# Stepper_Hat_Trio_V3_9.net
KiCad netlist of a schematic drawn in EasyEDA
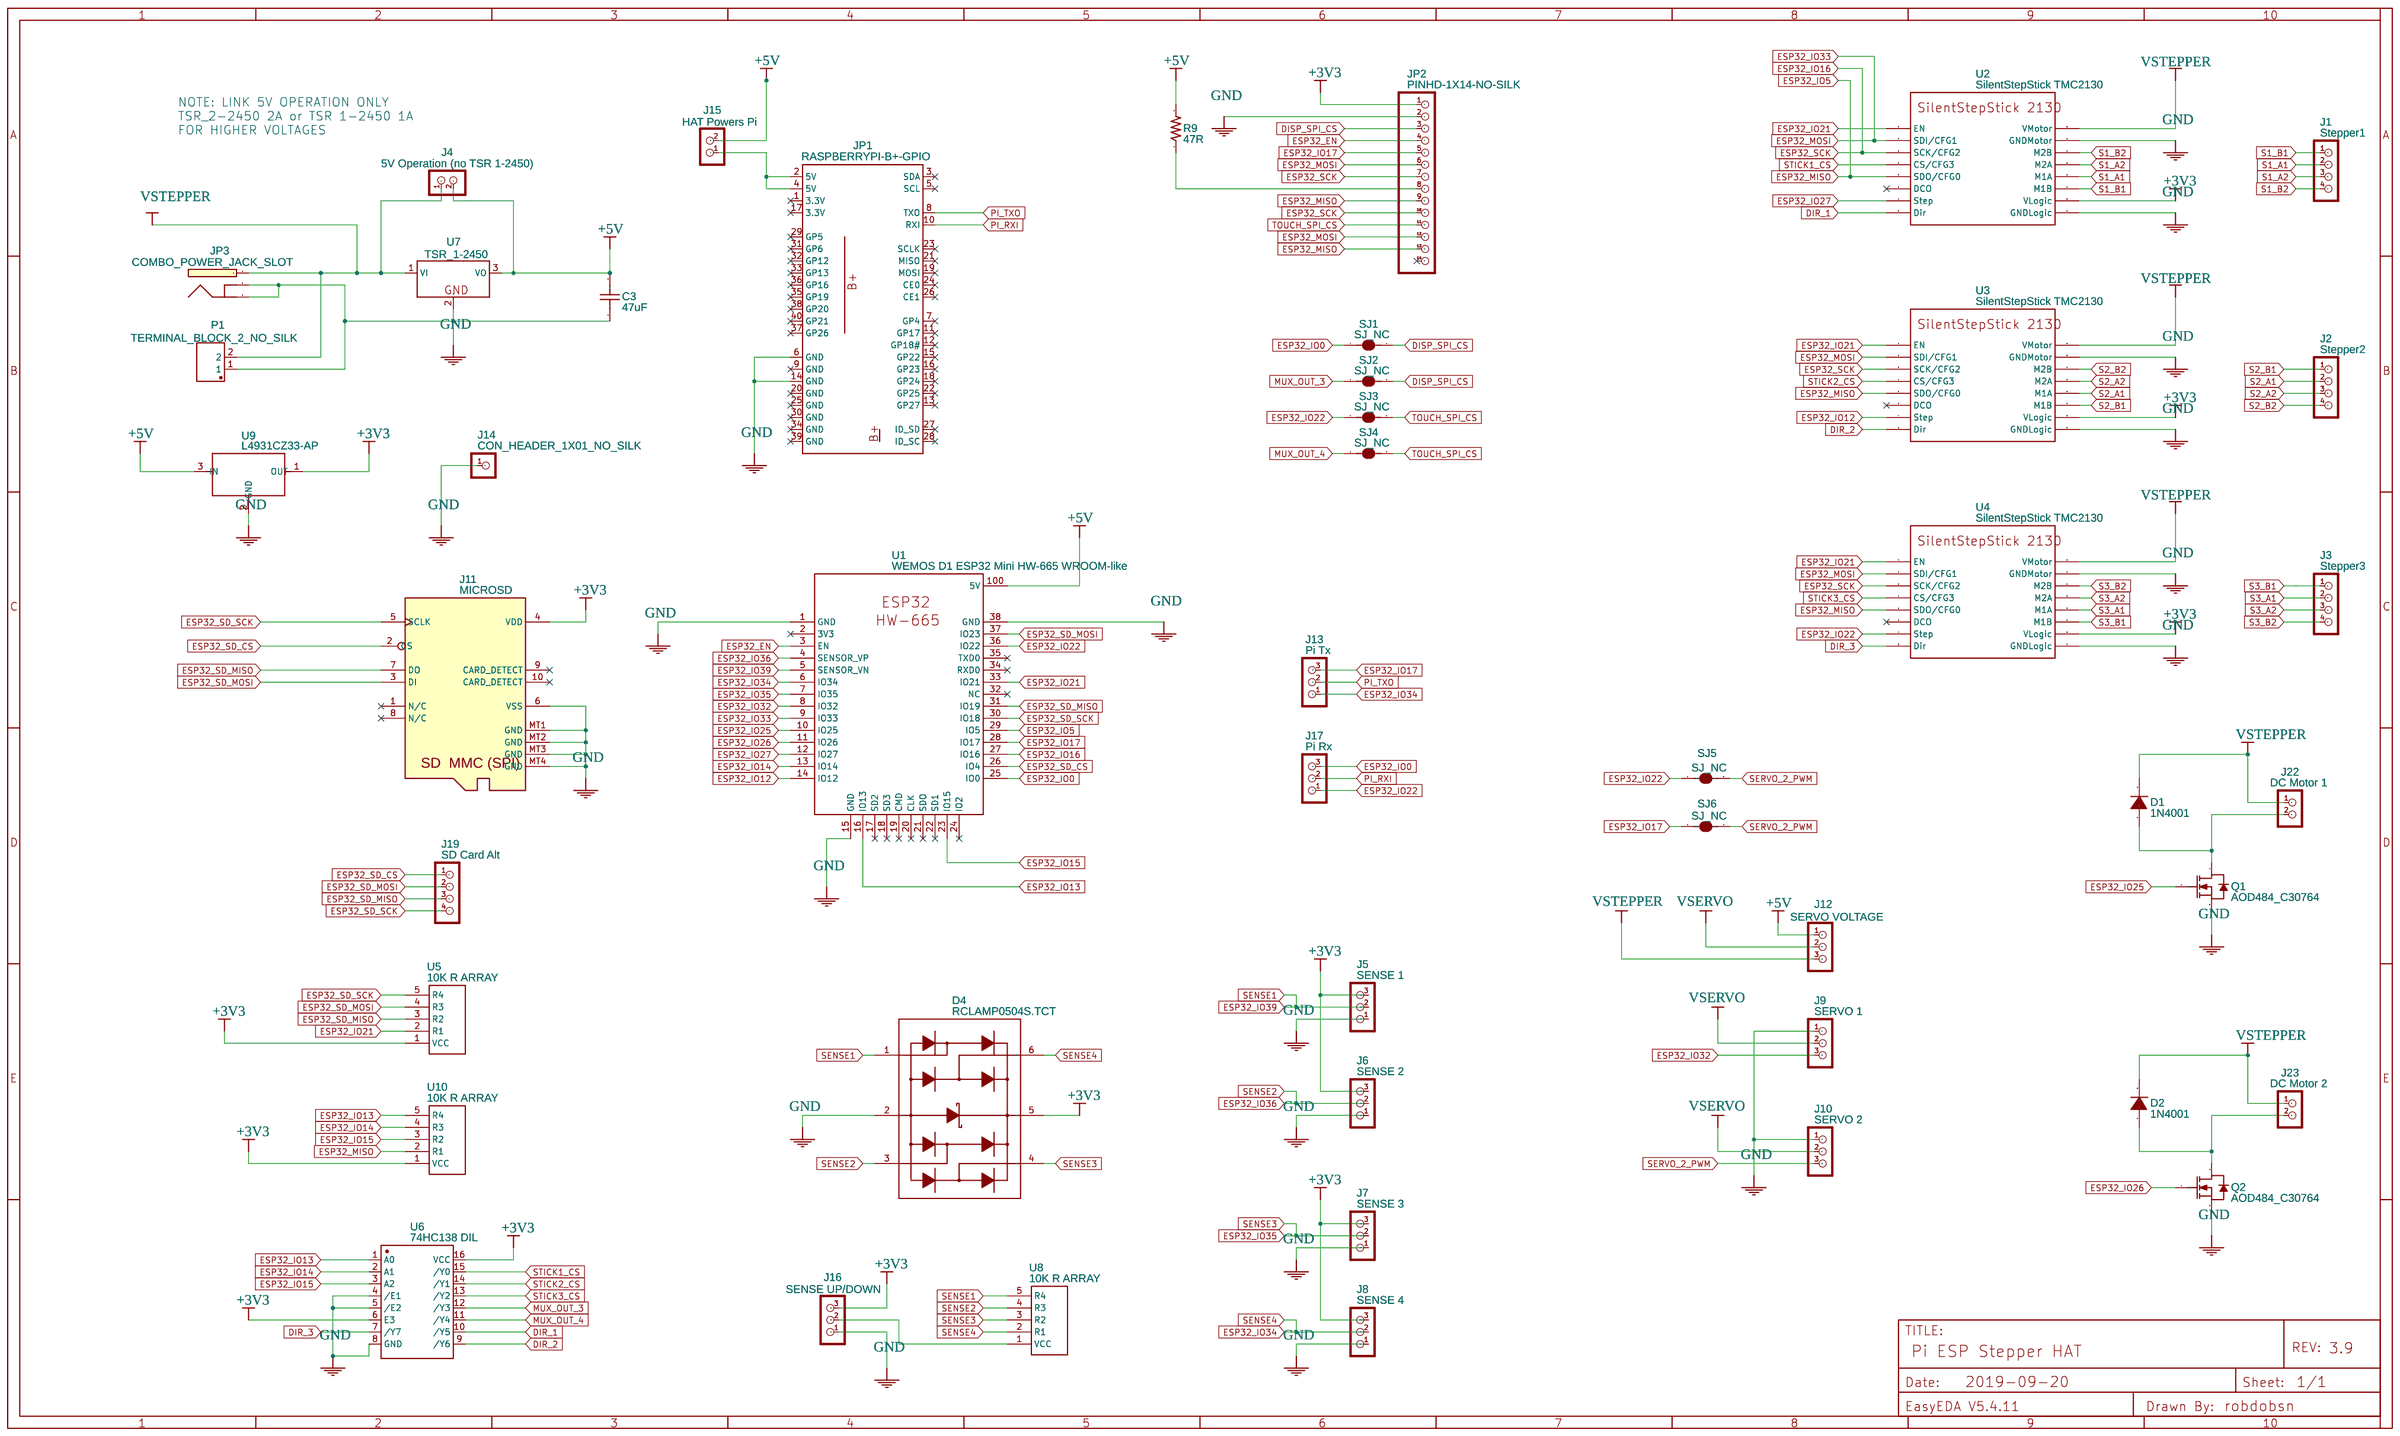
[diagram p0: schematic sheet]

(export (version "E")
  (design (tool "Eeschema 10.0.6"))
  (components
    (comp (ref "C3")
      (value "47uF")
      (fields
        (field (name "BOM_Manufacturer Part") "GRM31CR60J107ME39L")
        (field (name "BOM_Supplier Part") "C77085")
      )
      (libsource (lib "") (part "GRM31CR60J107ME39L"))
    )
    (comp (ref "D1")
      (value "1N4001")
      (fields (field (name "BOM_Supplier Part") "C82804"))
      (libsource (lib "") (part "Unknown_1690_660"))
    )
    (comp (ref "D2")
      (value "1N4001")
      (fields (field (name "BOM_Supplier Part") "C82804"))
      (libsource (lib "") (part "Unknown_1690_910"))
    )
    (comp (ref "D4")
      (value "RCLAMP0504S.TCT")
      (fields (field (name "BOM_Supplier Part") "C132260"))
      (libsource (lib "") (part "Unknown_710_920"))
    )
    (comp (ref "J1")
      (value "Stepper1")
      (fields (field (name "BOM_Manufacturer Part") "?"))
      (libsource (lib "") (part "Unknown_1840_130"))
    )
    (comp (ref "J2")
      (value "Stepper2")
      (fields (field (name "BOM_Manufacturer Part") "?"))
      (libsource (lib "") (part "Unknown_1840_310"))
    )
    (comp (ref "J3")
      (value "Stepper3")
      (fields (field (name "BOM_Manufacturer Part") "?"))
      (libsource (lib "") (part "Unknown_1840_490"))
    )
    (comp (ref "J4")
      (value "5V Operation (no TSR 1-2450)")
      (fields (field (name "BOM_Manufacturer Part") "?"))
      (libsource (lib "") (part "Unknown_280_150"))
    )
    (comp (ref "J5")
      (value "SENSE 1")
      (fields (field (name "BOM_Manufacturer Part") "?"))
      (libsource (lib "") (part "Unknown_1050_830"))
    )
    (comp (ref "J6")
      (value "SENSE 2")
      (fields (field (name "BOM_Manufacturer Part") "?"))
      (libsource (lib "") (part "Unknown_1050_910"))
    )
    (comp (ref "J7")
      (value "SENSE 3")
      (fields (field (name "BOM_Manufacturer Part") "?"))
      (libsource (lib "") (part "Unknown_1050_1020"))
    )
    (comp (ref "J8")
      (value "SENSE 4")
      (fields (field (name "BOM_Manufacturer Part") "?"))
      (libsource (lib "") (part "Unknown_1050_1100"))
    )
    (comp (ref "J9")
      (value "SERVO 1")
      (fields (field (name "BOM_Manufacturer Part") "?"))
      (libsource (lib "") (part "Unknown_1420_860"))
    )
    (comp (ref "J10")
      (value "SERVO 2")
      (fields (field (name "BOM_Manufacturer Part") "?"))
      (libsource (lib "") (part "Unknown_1420_950"))
    )
    (comp (ref "J11")
      (value "MICROSD")
      (fields (field (name "BOM_Manufacturer Part") "?") (field (name "BOM_Supplier Part") "WM11190CT-ND"))
      (libsource (lib "") (part "Unknown_310_540"))
    )
    (comp (ref "J12")
      (value "SERVO VOLTAGE")
      (fields (field (name "BOM_Manufacturer Part") "?"))
      (libsource (lib "") (part "Unknown_1420_780"))
    )
    (comp (ref "J13")
      (value "Pi Tx")
      (fields (field (name "BOM_Manufacturer Part") "?"))
      (libsource (lib "") (part "Unknown_1010_560"))
    )
    (comp (ref "J14") (value "CON_HEADER_1X01_NO_SILK") (libsource (lib "") (part "Unknown_320_380")))
    (comp (ref "J15")
      (value "HAT Powers Pi")
      (fields (field (name "BOM_Manufacturer Part") "?"))
      (libsource (lib "") (part "Unknown_510_120"))
    )
    (comp (ref "J16")
      (value "SENSE UP/DOWN")
      (fields (field (name "BOM_Manufacturer Part") "?"))
      (libsource (lib "") (part "Unknown_610_1090"))
    )
    (comp (ref "J17")
      (value "Pi Rx")
      (fields (field (name "BOM_Manufacturer Part") "?"))
      (libsource (lib "") (part "Unknown_1010_640"))
    )
    (comp (ref "J19") (value "SD Card Alt") (libsource (lib "") (part "Unknown_280_730")))
    (comp (ref "J22")
      (value "DC Motor 1")
      (fields (field (name "BOM_Manufacturer Part") "?"))
      (libsource (lib "") (part "Unknown_1810_660"))
    )
    (comp (ref "J23")
      (value "DC Motor 2")
      (fields (field (name "BOM_Manufacturer Part") "?"))
      (libsource (lib "") (part "Unknown_1810_910"))
    )
    (comp (ref "JP1")
      (value "RASPBERRYPI-B+-GPIO")
      (fields (field (name "BOM_Manufacturer Part") "?"))
      (libsource (lib "") (part "Unknown_630_240"))
    )
    (comp (ref "JP2") (value "PINHD-1X14-NO-SILK") (libsource (lib "") (part "Unknown_1090_150")))
    (comp (ref "JP3") (value "COMBO_POWER_JACK_SLOT") (libsource (lib "") (part "Unknown_100_230")))
    (comp (ref "P1")
      (value "TERMINAL_BLOCK_2_NO_SILK")
      (fields
        (field (name "BOM_Manufacturer Part") "WJ2EDGV-5.08-2P")
        (field (name "BOM_Supplier Part") "C8461")
      )
      (libsource (lib "") (part "Unknown_100_310"))
    )
    (comp (ref "Q1")
      (value "AOD484_C30764")
      (fields (field (name "BOM_Manufacturer Part") "AOD484") (field (name "BOM_Supplier Part") "C30764"))
      (libsource (lib "") (part "Unknown_1740_730"))
    )
    (comp (ref "Q2")
      (value "AOD484_C30764")
      (fields (field (name "BOM_Manufacturer Part") "AOD484") (field (name "BOM_Supplier Part") "C30764"))
      (libsource (lib "") (part "Unknown_1740_980"))
    )
    (comp (ref "R9")
      (value "47R")
      (fields (field (name "BOM_Manufacturer Part") "?"))
      (libsource (lib "") (part "Unknown_890_100"))
    )
    (comp (ref "SJ1") (value "SJ_NC") (libsource (lib "") (part "Unknown_1050_280")))
    (comp (ref "SJ2") (value "SJ_NC") (libsource (lib "") (part "Unknown_1050_310")))
    (comp (ref "SJ3") (value "SJ_NC") (libsource (lib "") (part "Unknown_1050_340")))
    (comp (ref "SJ4") (value "SJ_NC") (libsource (lib "") (part "Unknown_1050_370")))
    (comp (ref "SJ5") (value "SJ_NC") (libsource (lib "") (part "Unknown_1330_640")))
    (comp (ref "SJ6") (value "SJ_NC") (libsource (lib "") (part "Unknown_1330_680")))
    (comp (ref "U1")
      (value "WEMOS D1 ESP32 Mini HW-665 WROOM-like")
      (fields (field (name "BOM_Supplier Part") "WEMOS_D1_ESP32"))
      (libsource (lib "") (part "Unknown_570_660"))
    )
    (comp (ref "U2")
      (value "SilentStepStick TMC2130")
      (fields (field (name "BOM_Supplier Part") "20160027"))
      (libsource (lib "") (part "Unknown_1480_100"))
    )
    (comp (ref "U3")
      (value "SilentStepStick TMC2130")
      (fields (field (name "BOM_Supplier Part") "20160027"))
      (libsource (lib "") (part "Unknown_1480_280"))
    )
    (comp (ref "U4")
      (value "SilentStepStick TMC2130")
      (fields (field (name "BOM_Supplier Part") "20160027"))
      (libsource (lib "") (part "Unknown_1480_460"))
    )
    (comp (ref "U5")
      (value "10K R ARRAY")
      (fields
        (field (name "BOM_Manufacturer Part") "4605X-AP1-103LF")
        (field (name "BOM_Supplier Part") "652-4605X-AP1-103LF")
      )
      (libsource (lib "") (part "Unknown_270_820"))
    )
    (comp (ref "U6")
      (value "74HC138 DIL")
      (fields (field (name "BOM_Manufacturer Part") "74HC138") (field (name "BOM_Supplier Part") "C2913"))
      (libsource (lib "") (part "Unknown_260_1060"))
    )
    (comp (ref "U7")
      (value "TSR_1-2450")
      (fields
        (field (name "BOM_Manufacturer Part") "TSR 1-2433")
        (field (name "BOM_Supplier Part") "1696319")
      )
      (libsource (lib "") (part "Unknown_290_220"))
    )
    (comp (ref "U8")
      (value "10K R ARRAY")
      (fields
        (field (name "BOM_Manufacturer Part") "4605X-AP1-103LF")
        (field (name "BOM_Supplier Part") "652-4605X-AP1-103LF")
      )
      (libsource (lib "") (part "Unknown_770_1070"))
    )
    (comp (ref "U9") (value "L4931CZ33-AP") (libsource (lib "") (part "Unknown_120_400")))
    (comp (ref "U10")
      (value "10K R ARRAY")
      (fields
        (field (name "BOM_Manufacturer Part") "4605X-AP1-103LF")
        (field (name "BOM_Supplier Part") "652-4605X-AP1-103LF")
      )
      (libsource (lib "") (part "Unknown_270_920"))
    )
  )
  (nets
    (net (code "1") (name "+3V3") (class "Default")
      (node (ref "D4") (pin "5") (pinfunction "5_5") (pintype "input"))
      (node (ref "J11") (pin "4") (pinfunction "VDD_4") (pintype "unspecified"))
      (node (ref "J16") (pin "3") (pinfunction "3_3") (pintype "unspecified"))
      (node (ref "J5") (pin "3") (pinfunction "3_3") (pintype "unspecified"))
      (node (ref "J6") (pin "3") (pinfunction "3_3") (pintype "unspecified"))
      (node (ref "J7") (pin "3") (pinfunction "3_3") (pintype "unspecified"))
      (node (ref "J8") (pin "3") (pinfunction "3_3") (pintype "unspecified"))
      (node (ref "JP2") (pin "1") (pinfunction "1_1") (pintype "unspecified"))
      (node (ref "U10") (pin "1") (pinfunction "VCC_1") (pintype "unspecified"))
      (node (ref "U2") (pin "10") (pinfunction "VLogic_10") (pintype "unspecified"))
      (node (ref "U3") (pin "10") (pinfunction "VLogic_10") (pintype "unspecified"))
      (node (ref "U4") (pin "10") (pinfunction "VLogic_10") (pintype "unspecified"))
      (node (ref "U5") (pin "1") (pinfunction "VCC_1") (pintype "unspecified"))
      (node (ref "U6") (pin "16") (pinfunction "VCC_16") (pintype "unspecified"))
      (node (ref "U6") (pin "6") (pinfunction "E3_6") (pintype "unspecified"))
      (node (ref "U9") (pin "1") (pinfunction "OUT_1") (pintype "unspecified"))
    )
    (net (code "2") (name "+5V") (class "Default")
      (node (ref "C3") (pin "2") (pinfunction "2_2") (pintype "unspecified"))
      (node (ref "J12") (pin "1") (pinfunction "1_1") (pintype "unspecified"))
      (node (ref "J15") (pin "2") (pinfunction "2_2") (pintype "unspecified"))
      (node (ref "J4") (pin "2") (pinfunction "2_2") (pintype "unspecified"))
      (node (ref "R9") (pin "2") (pinfunction "2_2") (pintype "unspecified"))
      (node (ref "U1") (pin "100") (pinfunction "5V_100") (pintype "bidirectional"))
      (node (ref "U7") (pin "3") (pinfunction "VO_3") (pintype "passive"))
      (node (ref "U9") (pin "3") (pinfunction "IN_3") (pintype "unspecified"))
    )
    (net (code "3") (name "DIR_1") (class "Default")
      (node (ref "U2") (pin "8") (pinfunction "Dir_8") (pintype "unspecified"))
      (node (ref "U6") (pin "10") (pinfunction "/Y5_10") (pintype "unspecified"))
    )
    (net (code "4") (name "DIR_2") (class "Default")
      (node (ref "U3") (pin "8") (pinfunction "Dir_8") (pintype "unspecified"))
      (node (ref "U6") (pin "9") (pinfunction "/Y6_9") (pintype "unspecified"))
    )
    (net (code "5") (name "DIR_3") (class "Default")
      (node (ref "U4") (pin "8") (pinfunction "Dir_8") (pintype "unspecified"))
      (node (ref "U6") (pin "7") (pinfunction "/Y7_7") (pintype "unspecified"))
    )
    (net (code "6") (name "DISP_SPI_CS") (class "Default")
      (node (ref "JP2") (pin "3") (pinfunction "3_3") (pintype "unspecified"))
      (node (ref "SJ1") (pin "2") (pinfunction "2_2") (pintype "unspecified"))
      (node (ref "SJ2") (pin "2") (pinfunction "2_2") (pintype "unspecified"))
    )
    (net (code "7") (name "ESP32_EN") (class "Default")
      (node (ref "JP2") (pin "4") (pinfunction "4_4") (pintype "unspecified"))
      (node (ref "U1") (pin "3") (pinfunction "EN_3") (pintype "input"))
    )
    (net (code "8") (name "ESP32_IO0") (class "Default")
      (node (ref "J17") (pin "3") (pinfunction "3_3") (pintype "unspecified"))
      (node (ref "SJ1") (pin "1") (pinfunction "1_1") (pintype "unspecified"))
      (node (ref "U1") (pin "25") (pinfunction "IO0_25") (pintype "bidirectional"))
    )
    (net (code "9") (name "ESP32_IO5") (class "Default")
      (node (ref "JP2") (pin "13") (pinfunction "13_13") (pintype "unspecified"))
      (node (ref "JP2") (pin "9") (pinfunction "9_9") (pintype "unspecified"))
      (node (ref "U1") (pin "29") (pinfunction "IO5_29") (pintype "bidirectional"))
      (node (ref "U10") (pin "2") (pinfunction "R1_2") (pintype "unspecified"))
      (node (ref "U2") (pin "5") (pinfunction "SDO/CFG0_5") (pintype "unspecified"))
      (node (ref "U3") (pin "5") (pinfunction "SDO/CFG0_5") (pintype "unspecified"))
      (node (ref "U4") (pin "5") (pinfunction "SDO/CFG0_5") (pintype "unspecified"))
    )
    (net (code "10") (name "ESP32_IO12") (class "Default")
      (node (ref "U1") (pin "14") (pinfunction "IO12_14") (pintype "bidirectional"))
      (node (ref "U3") (pin "7") (pinfunction "Step_7") (pintype "unspecified"))
    )
    (net (code "11") (name "ESP32_IO13") (class "Default")
      (node (ref "U1") (pin "16") (pinfunction "IO13_16") (pintype "bidirectional"))
      (node (ref "U10") (pin "5") (pinfunction "R4_5") (pintype "unspecified"))
      (node (ref "U6") (pin "1") (pinfunction "A0_1") (pintype "unspecified"))
    )
    (net (code "12") (name "ESP32_IO14") (class "Default")
      (node (ref "U1") (pin "13") (pinfunction "IO14_13") (pintype "bidirectional"))
      (node (ref "U10") (pin "4") (pinfunction "R3_4") (pintype "unspecified"))
      (node (ref "U6") (pin "2") (pinfunction "A1_2") (pintype "unspecified"))
    )
    (net (code "13") (name "ESP32_IO15") (class "Default")
      (node (ref "U1") (pin "23") (pinfunction "IO15_23") (pintype "bidirectional"))
      (node (ref "U10") (pin "3") (pinfunction "R2_3") (pintype "unspecified"))
      (node (ref "U6") (pin "3") (pinfunction "A2_3") (pintype "unspecified"))
    )
    (net (code "14") (name "ESP32_IO16") (class "Default")
      (node (ref "JP2") (pin "10") (pinfunction "10_10") (pintype "unspecified"))
      (node (ref "JP2") (pin "7") (pinfunction "7_7") (pintype "unspecified"))
      (node (ref "U1") (pin "27") (pinfunction "IO16_27") (pintype "bidirectional"))
      (node (ref "U2") (pin "3") (pinfunction "SCK/CFG2_3") (pintype "unspecified"))
      (node (ref "U3") (pin "3") (pinfunction "SCK/CFG2_3") (pintype "unspecified"))
      (node (ref "U4") (pin "3") (pinfunction "SCK/CFG2_3") (pintype "unspecified"))
    )
    (net (code "15") (name "ESP32_IO17") (class "Default")
      (node (ref "J13") (pin "3") (pinfunction "3_3") (pintype "unspecified"))
      (node (ref "JP2") (pin "5") (pinfunction "5_5") (pintype "unspecified"))
      (node (ref "SJ6") (pin "1") (pinfunction "1_1") (pintype "unspecified"))
      (node (ref "U1") (pin "28") (pinfunction "IO17_28") (pintype "bidirectional"))
    )
    (net (code "16") (name "ESP32_IO21") (class "Default")
      (node (ref "U1") (pin "33") (pinfunction "IO21_33") (pintype "bidirectional"))
      (node (ref "U2") (pin "1") (pinfunction "EN_1") (pintype "unspecified"))
      (node (ref "U3") (pin "1") (pinfunction "EN_1") (pintype "unspecified"))
      (node (ref "U4") (pin "1") (pinfunction "EN_1") (pintype "unspecified"))
      (node (ref "U5") (pin "2") (pinfunction "R1_2") (pintype "unspecified"))
    )
    (net (code "17") (name "ESP32_IO22") (class "Default")
      (node (ref "J17") (pin "1") (pinfunction "1_1") (pintype "unspecified"))
      (node (ref "SJ3") (pin "1") (pinfunction "1_1") (pintype "unspecified"))
      (node (ref "SJ5") (pin "1") (pinfunction "1_1") (pintype "unspecified"))
      (node (ref "U1") (pin "36") (pinfunction "IO22_36") (pintype "bidirectional"))
      (node (ref "U4") (pin "7") (pinfunction "Step_7") (pintype "unspecified"))
    )
    (net (code "18") (name "ESP32_IO25") (class "Default")
      (node (ref "Q1") (pin "1") (pinfunction "G_1") (pintype "unspecified"))
      (node (ref "U1") (pin "10") (pinfunction "IO25_10") (pintype "bidirectional"))
    )
    (net (code "19") (name "ESP32_IO26") (class "Default")
      (node (ref "Q2") (pin "1") (pinfunction "G_1") (pintype "unspecified"))
      (node (ref "U1") (pin "11") (pinfunction "IO26_11") (pintype "bidirectional"))
    )
    (net (code "20") (name "ESP32_IO27") (class "Default")
      (node (ref "U1") (pin "12") (pinfunction "IO27_12") (pintype "bidirectional"))
      (node (ref "U2") (pin "7") (pinfunction "Step_7") (pintype "unspecified"))
    )
    (net (code "21") (name "ESP32_IO32") (class "Default")
      (node (ref "J9") (pin "3") (pinfunction "3_3") (pintype "unspecified"))
      (node (ref "U1") (pin "8") (pinfunction "IO32_8") (pintype "bidirectional"))
    )
    (net (code "22") (name "ESP32_IO33") (class "Default")
      (node (ref "JP2") (pin "12") (pinfunction "12_12") (pintype "unspecified"))
      (node (ref "JP2") (pin "6") (pinfunction "6_6") (pintype "unspecified"))
      (node (ref "U1") (pin "9") (pinfunction "IO33_9") (pintype "bidirectional"))
      (node (ref "U2") (pin "2") (pinfunction "SDI/CFG1_2") (pintype "unspecified"))
      (node (ref "U3") (pin "2") (pinfunction "SDI/CFG1_2") (pintype "unspecified"))
      (node (ref "U4") (pin "2") (pinfunction "SDI/CFG1_2") (pintype "unspecified"))
    )
    (net (code "23") (name "ESP32_IO34") (class "Default")
      (node (ref "D4") (pin "6") (pinfunction "6_6") (pintype "input"))
      (node (ref "J13") (pin "1") (pinfunction "1_1") (pintype "unspecified"))
      (node (ref "J8") (pin "2") (pinfunction "2_2") (pintype "unspecified"))
      (node (ref "U1") (pin "6") (pinfunction "IO34_6") (pintype "bidirectional"))
      (node (ref "U8") (pin "2") (pinfunction "R1_2") (pintype "unspecified"))
    )
    (net (code "24") (name "ESP32_IO35") (class "Default")
      (node (ref "D4") (pin "4") (pinfunction "4_4") (pintype "input"))
      (node (ref "J7") (pin "2") (pinfunction "2_2") (pintype "unspecified"))
      (node (ref "U1") (pin "7") (pinfunction "IO35_7") (pintype "bidirectional"))
      (node (ref "U8") (pin "3") (pinfunction "R2_3") (pintype "unspecified"))
    )
    (net (code "25") (name "ESP32_IO36") (class "Default")
      (node (ref "D4") (pin "3") (pinfunction "3_3") (pintype "input"))
      (node (ref "J6") (pin "2") (pinfunction "2_2") (pintype "unspecified"))
      (node (ref "U1") (pin "4") (pinfunction "SENSOR_VP_4") (pintype "input"))
      (node (ref "U8") (pin "4") (pinfunction "R3_4") (pintype "unspecified"))
    )
    (net (code "26") (name "ESP32_IO39") (class "Default")
      (node (ref "D4") (pin "1") (pinfunction "1_1") (pintype "input"))
      (node (ref "J5") (pin "2") (pinfunction "2_2") (pintype "unspecified"))
      (node (ref "U1") (pin "5") (pinfunction "SENSOR_VN_5") (pintype "input"))
      (node (ref "U8") (pin "5") (pinfunction "R4_5") (pintype "unspecified"))
    )
    (net (code "27") (name "ESP32_SD_CS") (class "Default")
      (node (ref "J11") (pin "2") (pinfunction "CS_2") (pintype "input"))
      (node (ref "J19") (pin "1") (pinfunction "1_1") (pintype "unspecified"))
      (node (ref "U1") (pin "26") (pinfunction "IO4_26") (pintype "input"))
    )
    (net (code "28") (name "ESP32_SD_MISO") (class "Default")
      (node (ref "J11") (pin "7") (pinfunction "DO_7") (pintype "output"))
      (node (ref "J19") (pin "3") (pinfunction "3_3") (pintype "unspecified"))
      (node (ref "U1") (pin "31") (pinfunction "IO19_31") (pintype "bidirectional"))
      (node (ref "U5") (pin "3") (pinfunction "R2_3") (pintype "unspecified"))
    )
    (net (code "29") (name "ESP32_SD_MOSI") (class "Default")
      (node (ref "J11") (pin "3") (pinfunction "DI_3") (pintype "input"))
      (node (ref "J19") (pin "2") (pinfunction "2_2") (pintype "unspecified"))
      (node (ref "U1") (pin "37") (pinfunction "IO23_37") (pintype "bidirectional"))
      (node (ref "U5") (pin "4") (pinfunction "R3_4") (pintype "unspecified"))
    )
    (net (code "30") (name "ESP32_SD_SCK") (class "Default")
      (node (ref "J11") (pin "5") (pinfunction "SCLK_5") (pintype "input"))
      (node (ref "J19") (pin "4") (pinfunction "4_4") (pintype "unspecified"))
      (node (ref "U1") (pin "30") (pinfunction "IO18_30") (pintype "input"))
      (node (ref "U5") (pin "5") (pinfunction "R4_5") (pintype "unspecified"))
    )
    (net (code "31") (name "GND") (class "Default")
      (node (ref "C3") (pin "1") (pinfunction "1_1") (pintype "unspecified"))
      (node (ref "D4") (pin "2") (pinfunction "2_2") (pintype "input"))
      (node (ref "J10") (pin "1") (pinfunction "1_1") (pintype "unspecified"))
      (node (ref "J11") (pin "6") (pinfunction "VSS_6") (pintype "unspecified"))
      (node (ref "J11") (pin "MT1") (pinfunction "GND_MT1") (pintype "unspecified"))
      (node (ref "J11") (pin "MT2") (pinfunction "GND_MT2") (pintype "unspecified"))
      (node (ref "J11") (pin "MT3") (pinfunction "GND_MT3") (pintype "unspecified"))
      (node (ref "J11") (pin "MT4") (pinfunction "GND_MT4") (pintype "unspecified"))
      (node (ref "J14") (pin "1") (pinfunction "1_1") (pintype "unspecified"))
      (node (ref "J16") (pin "1") (pinfunction "1_1") (pintype "unspecified"))
      (node (ref "J5") (pin "1") (pinfunction "1_1") (pintype "unspecified"))
      (node (ref "J6") (pin "1") (pinfunction "1_1") (pintype "unspecified"))
      (node (ref "J7") (pin "1") (pinfunction "1_1") (pintype "unspecified"))
      (node (ref "J8") (pin "1") (pinfunction "1_1") (pintype "unspecified"))
      (node (ref "J9") (pin "1") (pinfunction "1_1") (pintype "unspecified"))
      (node (ref "JP1") (pin "14") (pinfunction "GND_14") (pintype "passive"))
      (node (ref "JP1") (pin "6") (pinfunction "GND_6") (pintype "passive"))
      (node (ref "JP2") (pin "2") (pinfunction "2_2") (pintype "unspecified"))
      (node (ref "JP3") (pin "2") (pinfunction "GNDBREAK_2") (pintype "unspecified"))
      (node (ref "JP3") (pin "3") (pinfunction "GND_3") (pintype "unspecified"))
      (node (ref "P1") (pin "1") (pinfunction "1_1") (pintype "unspecified"))
      (node (ref "Q1") (pin "3") (pinfunction "S_3") (pintype "unspecified"))
      (node (ref "Q2") (pin "3") (pinfunction "S_3") (pintype "unspecified"))
      (node (ref "U1") (pin "1") (pinfunction "GND_1") (pintype "bidirectional"))
      (node (ref "U1") (pin "15") (pinfunction "GND_15") (pintype "bidirectional"))
      (node (ref "U1") (pin "38") (pinfunction "GND_38") (pintype "bidirectional"))
      (node (ref "U2") (pin "15") (pinfunction "GNDMotor_15") (pintype "unspecified"))
      (node (ref "U2") (pin "9") (pinfunction "GNDLogic_9") (pintype "unspecified"))
      (node (ref "U3") (pin "15") (pinfunction "GNDMotor_15") (pintype "unspecified"))
      (node (ref "U3") (pin "9") (pinfunction "GNDLogic_9") (pintype "unspecified"))
      (node (ref "U4") (pin "15") (pinfunction "GNDMotor_15") (pintype "unspecified"))
      (node (ref "U4") (pin "9") (pinfunction "GNDLogic_9") (pintype "unspecified"))
      (node (ref "U6") (pin "4") (pinfunction "/E1_4") (pintype "unspecified"))
      (node (ref "U6") (pin "5") (pinfunction "/E2_5") (pintype "unspecified"))
      (node (ref "U6") (pin "8") (pinfunction "GND_8") (pintype "unspecified"))
      (node (ref "U7") (pin "2") (pinfunction "GND_2") (pintype "passive"))
      (node (ref "U9") (pin "2") (pinfunction "GND_2") (pintype "unspecified"))
    )
    (net (code "32") (name "MUX_OUT_3") (class "Default")
      (node (ref "SJ2") (pin "1") (pinfunction "1_1") (pintype "unspecified"))
      (node (ref "U6") (pin "12") (pinfunction "/Y3_12") (pintype "unspecified"))
    )
    (net (code "33") (name "MUX_OUT_4") (class "Default")
      (node (ref "SJ4") (pin "1") (pinfunction "1_1") (pintype "unspecified"))
      (node (ref "U6") (pin "11") (pinfunction "/Y4_11") (pintype "unspecified"))
    )
    (net (code "34") (name "Net-(D1-A)") (class "Default")
      (node (ref "D1") (pin "1") (pinfunction "A_1") (pintype "unspecified"))
      (node (ref "J22") (pin "2") (pinfunction "2_2") (pintype "unspecified"))
      (node (ref "Q1") (pin "4") (pinfunction "D_4") (pintype "unspecified"))
    )
    (net (code "35") (name "Net-(D2-A)") (class "Default")
      (node (ref "D2") (pin "1") (pinfunction "A_1") (pintype "unspecified"))
      (node (ref "J23") (pin "2") (pinfunction "2_2") (pintype "unspecified"))
      (node (ref "Q2") (pin "4") (pinfunction "D_4") (pintype "unspecified"))
    )
    (net (code "36") (name "Net-(J15-Pad1)") (class "Default")
      (node (ref "J15") (pin "1") (pinfunction "1_1") (pintype "unspecified"))
      (node (ref "JP1") (pin "2") (pinfunction "5V_2") (pintype "passive"))
      (node (ref "JP1") (pin "4") (pinfunction "5V_4") (pintype "passive"))
    )
    (net (code "37") (name "Net-(JP2-Pad8)") (class "Default")
      (node (ref "JP2") (pin "8") (pinfunction "8_8") (pintype "unspecified"))
      (node (ref "R9") (pin "1") (pinfunction "1_1") (pintype "unspecified"))
    )
    (net (code "38") (name "Net-(U8-VCC)") (class "Default")
      (node (ref "J16") (pin "2") (pinfunction "2_2") (pintype "unspecified"))
      (node (ref "U8") (pin "1") (pinfunction "VCC_1") (pintype "unspecified"))
    )
    (net (code "39") (name "PI_RXI") (class "Default")
      (node (ref "J17") (pin "2") (pinfunction "2_2") (pintype "unspecified"))
      (node (ref "JP1") (pin "10") (pinfunction "RXI_10") (pintype "input"))
    )
    (net (code "40") (name "PI_TXO") (class "Default")
      (node (ref "J13") (pin "2") (pinfunction "2_2") (pintype "unspecified"))
      (node (ref "JP1") (pin "8") (pinfunction "TXO_8") (pintype "output"))
    )
    (net (code "41") (name "S1_A1") (class "Default")
      (node (ref "J1") (pin "2") (pinfunction "2_2") (pintype "unspecified"))
      (node (ref "U2") (pin "12") (pinfunction "M1A_12") (pintype "unspecified"))
    )
    (net (code "42") (name "S1_A2") (class "Default")
      (node (ref "J1") (pin "3") (pinfunction "3_3") (pintype "unspecified"))
      (node (ref "U2") (pin "13") (pinfunction "M2A_13") (pintype "unspecified"))
    )
    (net (code "43") (name "S1_B1") (class "Default")
      (node (ref "J1") (pin "1") (pinfunction "1_1") (pintype "unspecified"))
      (node (ref "U2") (pin "11") (pinfunction "M1B_11") (pintype "unspecified"))
    )
    (net (code "44") (name "S1_B2") (class "Default")
      (node (ref "J1") (pin "4") (pinfunction "4_4") (pintype "unspecified"))
      (node (ref "U2") (pin "14") (pinfunction "M2B_14") (pintype "unspecified"))
    )
    (net (code "45") (name "S2_A1") (class "Default")
      (node (ref "J2") (pin "2") (pinfunction "2_2") (pintype "unspecified"))
      (node (ref "U3") (pin "12") (pinfunction "M1A_12") (pintype "unspecified"))
    )
    (net (code "46") (name "S2_A2") (class "Default")
      (node (ref "J2") (pin "3") (pinfunction "3_3") (pintype "unspecified"))
      (node (ref "U3") (pin "13") (pinfunction "M2A_13") (pintype "unspecified"))
    )
    (net (code "47") (name "S2_B1") (class "Default")
      (node (ref "J2") (pin "1") (pinfunction "1_1") (pintype "unspecified"))
      (node (ref "U3") (pin "11") (pinfunction "M1B_11") (pintype "unspecified"))
    )
    (net (code "48") (name "S2_B2") (class "Default")
      (node (ref "J2") (pin "4") (pinfunction "4_4") (pintype "unspecified"))
      (node (ref "U3") (pin "14") (pinfunction "M2B_14") (pintype "unspecified"))
    )
    (net (code "49") (name "S3_A1") (class "Default")
      (node (ref "J3") (pin "2") (pinfunction "2_2") (pintype "unspecified"))
      (node (ref "U4") (pin "12") (pinfunction "M1A_12") (pintype "unspecified"))
    )
    (net (code "50") (name "S3_A2") (class "Default")
      (node (ref "J3") (pin "3") (pinfunction "3_3") (pintype "unspecified"))
      (node (ref "U4") (pin "13") (pinfunction "M2A_13") (pintype "unspecified"))
    )
    (net (code "51") (name "S3_B1") (class "Default")
      (node (ref "J3") (pin "1") (pinfunction "1_1") (pintype "unspecified"))
      (node (ref "U4") (pin "11") (pinfunction "M1B_11") (pintype "unspecified"))
    )
    (net (code "52") (name "S3_B2") (class "Default")
      (node (ref "J3") (pin "4") (pinfunction "4_4") (pintype "unspecified"))
      (node (ref "U4") (pin "14") (pinfunction "M2B_14") (pintype "unspecified"))
    )
    (net (code "53") (name "SERVO_2_PWM") (class "Default")
      (node (ref "J10") (pin "3") (pinfunction "3_3") (pintype "unspecified"))
      (node (ref "SJ5") (pin "2") (pinfunction "2_2") (pintype "unspecified"))
      (node (ref "SJ6") (pin "2") (pinfunction "2_2") (pintype "unspecified"))
    )
    (net (code "54") (name "STICK1_CS") (class "Default")
      (node (ref "U2") (pin "4") (pinfunction "CS/CFG3_4") (pintype "unspecified"))
      (node (ref "U6") (pin "15") (pinfunction "/Y0_15") (pintype "unspecified"))
    )
    (net (code "55") (name "STICK2_CS") (class "Default")
      (node (ref "U3") (pin "4") (pinfunction "CS/CFG3_4") (pintype "unspecified"))
      (node (ref "U6") (pin "14") (pinfunction "/Y1_14") (pintype "unspecified"))
    )
    (net (code "56") (name "STICK3_CS") (class "Default")
      (node (ref "U4") (pin "4") (pinfunction "CS/CFG3_4") (pintype "unspecified"))
      (node (ref "U6") (pin "13") (pinfunction "/Y2_13") (pintype "unspecified"))
    )
    (net (code "57") (name "TOUCH_SPI_CS") (class "Default")
      (node (ref "JP2") (pin "11") (pinfunction "11_11") (pintype "unspecified"))
      (node (ref "SJ3") (pin "2") (pinfunction "2_2") (pintype "unspecified"))
      (node (ref "SJ4") (pin "2") (pinfunction "2_2") (pintype "unspecified"))
    )
    (net (code "58") (name "VSERVO") (class "Default")
      (node (ref "J10") (pin "2") (pinfunction "2_2") (pintype "unspecified"))
      (node (ref "J12") (pin "2") (pinfunction "2_2") (pintype "unspecified"))
      (node (ref "J9") (pin "2") (pinfunction "2_2") (pintype "unspecified"))
    )
    (net (code "59") (name "VSTEPPER") (class "Default")
      (node (ref "D1") (pin "2") (pinfunction "K_2") (pintype "unspecified"))
      (node (ref "D2") (pin "2") (pinfunction "K_2") (pintype "unspecified"))
      (node (ref "J12") (pin "3") (pinfunction "3_3") (pintype "unspecified"))
      (node (ref "J22") (pin "1") (pinfunction "1_1") (pintype "unspecified"))
      (node (ref "J23") (pin "1") (pinfunction "1_1") (pintype "unspecified"))
      (node (ref "J4") (pin "1") (pinfunction "1_1") (pintype "unspecified"))
      (node (ref "JP3") (pin "1") (pinfunction "PWR_1") (pintype "unspecified"))
      (node (ref "P1") (pin "2") (pinfunction "2_2") (pintype "unspecified"))
      (node (ref "U2") (pin "16") (pinfunction "VMotor_16") (pintype "unspecified"))
      (node (ref "U3") (pin "16") (pinfunction "VMotor_16") (pintype "unspecified"))
      (node (ref "U4") (pin "16") (pinfunction "VMotor_16") (pintype "unspecified"))
      (node (ref "U7") (pin "1") (pinfunction "VI_1") (pintype "unspecified"))
    )
    (net (code "60") (name "unconnected-(J11-CARD_DETECT-Pad9)") (class "Default")
      (node (ref "J11") (pin "9") (pinfunction "CARD_DETECT_9") (pintype "unspecified+no_connect"))
    )
    (net (code "61") (name "unconnected-(J11-CARD_DETECT-Pad10)") (class "Default")
      (node (ref "J11") (pin "10") (pinfunction "CARD_DETECT_10") (pintype "unspecified+no_connect"))
    )
    (net (code "62") (name "unconnected-(J11-N{slash}C-Pad1)") (class "Default")
      (node (ref "J11") (pin "1") (pinfunction "N/C_1") (pintype "unspecified+no_connect"))
    )
    (net (code "63") (name "unconnected-(J11-N{slash}C-Pad8)") (class "Default")
      (node (ref "J11") (pin "8") (pinfunction "N/C_8") (pintype "unspecified+no_connect"))
    )
    (net (code "64") (name "unconnected-(JP1-3.3V-Pad1)") (class "Default")
      (node (ref "JP1") (pin "1") (pinfunction "3.3V_1") (pintype "passive+no_connect"))
    )
    (net (code "65") (name "unconnected-(JP1-3.3V-Pad17)") (class "Default")
      (node (ref "JP1") (pin "17") (pinfunction "3.3V_17") (pintype "passive+no_connect"))
    )
    (net (code "66") (name "unconnected-(JP1-CE0-Pad24)") (class "Default")
      (node (ref "JP1") (pin "24") (pinfunction "CE0_24") (pintype "output+no_connect"))
    )
    (net (code "67") (name "unconnected-(JP1-CE1-Pad26)") (class "Default")
      (node (ref "JP1") (pin "26") (pinfunction "CE1_26") (pintype "output+no_connect"))
    )
    (net (code "68") (name "unconnected-(JP1-GND-Pad9)") (class "Default")
      (node (ref "JP1") (pin "9") (pinfunction "GND_9") (pintype "passive+no_connect"))
    )
    (net (code "69") (name "unconnected-(JP1-GND-Pad20)") (class "Default")
      (node (ref "JP1") (pin "20") (pinfunction "GND_20") (pintype "passive+no_connect"))
    )
    (net (code "70") (name "unconnected-(JP1-GND-Pad25)") (class "Default")
      (node (ref "JP1") (pin "25") (pinfunction "GND_25") (pintype "passive+no_connect"))
    )
    (net (code "71") (name "unconnected-(JP1-GND-Pad30)") (class "Default")
      (node (ref "JP1") (pin "30") (pinfunction "GND_30") (pintype "passive+no_connect"))
    )
    (net (code "72") (name "unconnected-(JP1-GND-Pad34)") (class "Default")
      (node (ref "JP1") (pin "34") (pinfunction "GND_34") (pintype "passive+no_connect"))
    )
    (net (code "73") (name "unconnected-(JP1-GND-Pad39)") (class "Default")
      (node (ref "JP1") (pin "39") (pinfunction "GND_39") (pintype "passive+no_connect"))
    )
    (net (code "74") (name "unconnected-(JP1-GP4-Pad7)") (class "Default")
      (node (ref "JP1") (pin "7") (pinfunction "GP4_7") (pintype "unspecified+no_connect"))
    )
    (net (code "75") (name "unconnected-(JP1-GP5-Pad29)") (class "Default")
      (node (ref "JP1") (pin "29") (pinfunction "GP5_29") (pintype "unspecified+no_connect"))
    )
    (net (code "76") (name "unconnected-(JP1-GP6-Pad31)") (class "Default")
      (node (ref "JP1") (pin "31") (pinfunction "GP6_31") (pintype "unspecified+no_connect"))
    )
    (net (code "77") (name "unconnected-(JP1-GP12-Pad32)") (class "Default")
      (node (ref "JP1") (pin "32") (pinfunction "GP12_32") (pintype "unspecified+no_connect"))
    )
    (net (code "78") (name "unconnected-(JP1-GP13-Pad33)") (class "Default")
      (node (ref "JP1") (pin "33") (pinfunction "GP13_33") (pintype "unspecified+no_connect"))
    )
    (net (code "79") (name "unconnected-(JP1-GP16-Pad36)") (class "Default")
      (node (ref "JP1") (pin "36") (pinfunction "GP16_36") (pintype "unspecified+no_connect"))
    )
    (net (code "80") (name "unconnected-(JP1-GP17-Pad11)") (class "Default")
      (node (ref "JP1") (pin "11") (pinfunction "GP17_11") (pintype "unspecified+no_connect"))
    )
    (net (code "81") (name "unconnected-(JP1-GP18#-Pad12)") (class "Default")
      (node (ref "JP1") (pin "12") (pinfunction "GP18#_12") (pintype "unspecified+no_connect"))
    )
    (net (code "82") (name "unconnected-(JP1-GP19-Pad35)") (class "Default")
      (node (ref "JP1") (pin "35") (pinfunction "GP19_35") (pintype "unspecified+no_connect"))
    )
    (net (code "83") (name "unconnected-(JP1-GP20-Pad38)") (class "Default")
      (node (ref "JP1") (pin "38") (pinfunction "GP20_38") (pintype "unspecified+no_connect"))
    )
    (net (code "84") (name "unconnected-(JP1-GP21-Pad40)") (class "Default")
      (node (ref "JP1") (pin "40") (pinfunction "GP21_40") (pintype "unspecified+no_connect"))
    )
    (net (code "85") (name "unconnected-(JP1-GP22-Pad15)") (class "Default")
      (node (ref "JP1") (pin "15") (pinfunction "GP22_15") (pintype "unspecified+no_connect"))
    )
    (net (code "86") (name "unconnected-(JP1-GP23-Pad16)") (class "Default")
      (node (ref "JP1") (pin "16") (pinfunction "GP23_16") (pintype "unspecified+no_connect"))
    )
    (net (code "87") (name "unconnected-(JP1-GP24-Pad18)") (class "Default")
      (node (ref "JP1") (pin "18") (pinfunction "GP24_18") (pintype "unspecified+no_connect"))
    )
    (net (code "88") (name "unconnected-(JP1-GP25-Pad22)") (class "Default")
      (node (ref "JP1") (pin "22") (pinfunction "GP25_22") (pintype "unspecified+no_connect"))
    )
    (net (code "89") (name "unconnected-(JP1-GP26-Pad37)") (class "Default")
      (node (ref "JP1") (pin "37") (pinfunction "GP26_37") (pintype "unspecified+no_connect"))
    )
    (net (code "90") (name "unconnected-(JP1-GP27-Pad13)") (class "Default")
      (node (ref "JP1") (pin "13") (pinfunction "GP27_13") (pintype "unspecified+no_connect"))
    )
    (net (code "91") (name "unconnected-(JP1-ID_SC-Pad28)") (class "Default")
      (node (ref "JP1") (pin "28") (pinfunction "ID_SC_28") (pintype "unspecified+no_connect"))
    )
    (net (code "92") (name "unconnected-(JP1-ID_SD-Pad27)") (class "Default")
      (node (ref "JP1") (pin "27") (pinfunction "ID_SD_27") (pintype "unspecified+no_connect"))
    )
    (net (code "93") (name "unconnected-(JP1-MISO-Pad21)") (class "Default")
      (node (ref "JP1") (pin "21") (pinfunction "MISO_21") (pintype "input+no_connect"))
    )
    (net (code "94") (name "unconnected-(JP1-MOSI-Pad19)") (class "Default")
      (node (ref "JP1") (pin "19") (pinfunction "MOSI_19") (pintype "output+no_connect"))
    )
    (net (code "95") (name "unconnected-(JP1-SCL-Pad5)") (class "Default")
      (node (ref "JP1") (pin "5") (pinfunction "SCL_5") (pintype "unspecified+no_connect"))
    )
    (net (code "96") (name "unconnected-(JP1-SCLK-Pad23)") (class "Default")
      (node (ref "JP1") (pin "23") (pinfunction "SCLK_23") (pintype "output+no_connect"))
    )
    (net (code "97") (name "unconnected-(JP1-SDA-Pad3)") (class "Default")
      (node (ref "JP1") (pin "3") (pinfunction "SDA_3") (pintype "unspecified+no_connect"))
    )
    (net (code "98") (name "unconnected-(JP2-Pad14)") (class "Default")
      (node (ref "JP2") (pin "14") (pinfunction "14_14") (pintype "unspecified+no_connect"))
    )
    (net (code "99") (name "unconnected-(U1-3V3-Pad2)") (class "Default")
      (node (ref "U1") (pin "2") (pinfunction "3V3_2") (pintype "bidirectional+no_connect"))
    )
    (net (code "100") (name "unconnected-(U1-CLK-Pad20)") (class "Default")
      (node (ref "U1") (pin "20") (pinfunction "CLK_20") (pintype "input+no_connect"))
    )
    (net (code "101") (name "unconnected-(U1-CMD-Pad19)") (class "Default")
      (node (ref "U1") (pin "19") (pinfunction "CMD_19") (pintype "bidirectional+no_connect"))
    )
    (net (code "102") (name "unconnected-(U1-IO2-Pad24)") (class "Default")
      (node (ref "U1") (pin "24") (pinfunction "IO2_24") (pintype "bidirectional+no_connect"))
    )
    (net (code "103") (name "unconnected-(U1-NC-Pad32)") (class "Default")
      (node (ref "U1") (pin "32") (pinfunction "NC_32") (pintype "bidirectional+no_connect"))
    )
    (net (code "104") (name "unconnected-(U1-RXD0-Pad34)") (class "Default")
      (node (ref "U1") (pin "34") (pinfunction "RXD0_34") (pintype "bidirectional+no_connect"))
    )
    (net (code "105") (name "unconnected-(U1-SD1-Pad22)") (class "Default")
      (node (ref "U1") (pin "22") (pinfunction "SD1_22") (pintype "bidirectional+no_connect"))
    )
    (net (code "106") (name "unconnected-(U1-SD2-Pad17)") (class "Default")
      (node (ref "U1") (pin "17") (pinfunction "SD2_17") (pintype "bidirectional+no_connect"))
    )
    (net (code "107") (name "unconnected-(U1-SD3-Pad18)") (class "Default")
      (node (ref "U1") (pin "18") (pinfunction "SD3_18") (pintype "bidirectional+no_connect"))
    )
    (net (code "108") (name "unconnected-(U1-SDO-Pad21)") (class "Default")
      (node (ref "U1") (pin "21") (pinfunction "SDO_21") (pintype "bidirectional+no_connect"))
    )
    (net (code "109") (name "unconnected-(U1-TXD0-Pad35)") (class "Default")
      (node (ref "U1") (pin "35") (pinfunction "TXD0_35") (pintype "bidirectional+no_connect"))
    )
    (net (code "110") (name "unconnected-(U2-DCO-Pad6)") (class "Default")
      (node (ref "U2") (pin "6") (pinfunction "DCO_6") (pintype "unspecified+no_connect"))
    )
    (net (code "111") (name "unconnected-(U3-DCO-Pad6)") (class "Default")
      (node (ref "U3") (pin "6") (pinfunction "DCO_6") (pintype "unspecified+no_connect"))
    )
    (net (code "112") (name "unconnected-(U4-DCO-Pad6)") (class "Default")
      (node (ref "U4") (pin "6") (pinfunction "DCO_6") (pintype "unspecified+no_connect"))
    )
  )
)
